# castaway_rp2040.net
KiCad netlist of a schematic drawn in EAGLE
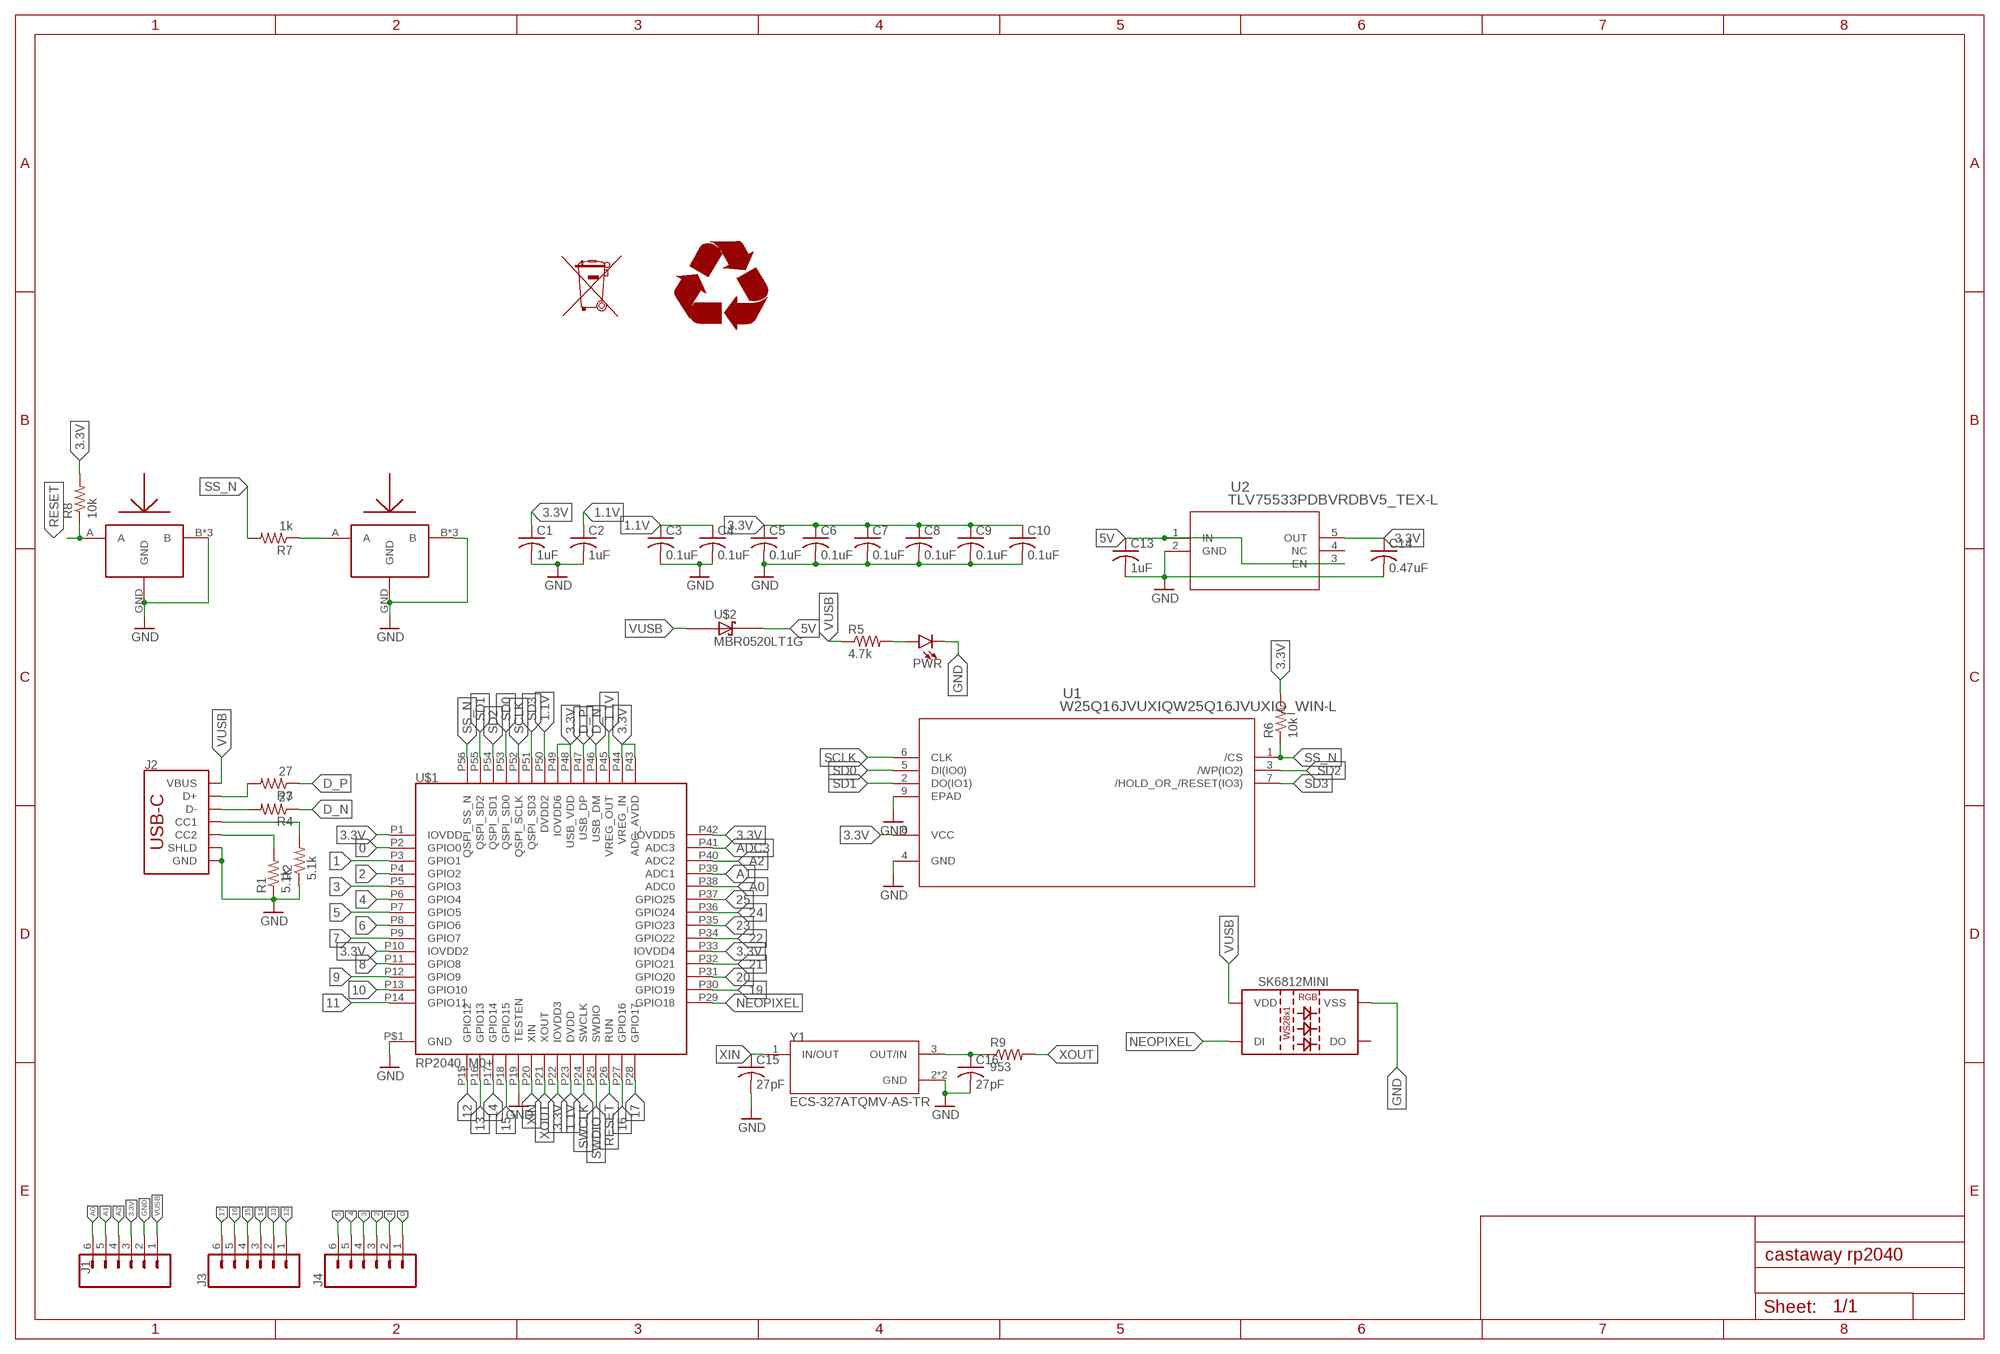
[diagram p0: schematic, sheet 1]

(export (version "E")
  (design (tool "Eeschema 10.0.6"))
  (components
    (comp (ref "C1")
      (value "1uF")
      (footprint "eagle-import:C0603")
      (libsource (lib "eagle-import") (part "C-USC0603"))
    )
    (comp (ref "C2")
      (value "1uF")
      (footprint "eagle-import:C0603")
      (libsource (lib "eagle-import") (part "C-USC0603"))
    )
    (comp (ref "C3")
      (value "0.1uF")
      (footprint "eagle-import:C0603")
      (libsource (lib "eagle-import") (part "C-USC0603"))
    )
    (comp (ref "C4")
      (value "0.1uF")
      (footprint "eagle-import:C0603")
      (libsource (lib "eagle-import") (part "C-USC0603"))
    )
    (comp (ref "C5")
      (value "0.1uF")
      (footprint "eagle-import:C0603")
      (libsource (lib "eagle-import") (part "C-USC0603"))
    )
    (comp (ref "C6")
      (value "0.1uF")
      (footprint "eagle-import:C0603")
      (libsource (lib "eagle-import") (part "C-USC0603"))
    )
    (comp (ref "C7")
      (value "0.1uF")
      (footprint "eagle-import:C0603")
      (libsource (lib "eagle-import") (part "C-USC0603"))
    )
    (comp (ref "C8")
      (value "0.1uF")
      (footprint "eagle-import:C0603")
      (libsource (lib "eagle-import") (part "C-USC0603"))
    )
    (comp (ref "C9")
      (value "0.1uF")
      (footprint "eagle-import:C0603")
      (libsource (lib "eagle-import") (part "C-USC0603"))
    )
    (comp (ref "C10")
      (value "0.1uF")
      (footprint "eagle-import:C0603")
      (libsource (lib "eagle-import") (part "C-USC0603"))
    )
    (comp (ref "C13")
      (value "1uF")
      (footprint "eagle-import:C0603")
      (libsource (lib "eagle-import") (part "C-USC0603"))
    )
    (comp (ref "C14")
      (value "0.47uF")
      (footprint "eagle-import:C0603")
      (libsource (lib "eagle-import") (part "C-USC0603"))
    )
    (comp (ref "C15")
      (value "27pF")
      (footprint "eagle-import:C0402")
      (libsource (lib "eagle-import") (part "C-USC0402"))
    )
    (comp (ref "C16")
      (value "27pF")
      (footprint "eagle-import:C0402")
      (libsource (lib "eagle-import") (part "C-USC0402"))
    )
    (comp (ref "J1")
      (value "CONN_06LONGPADS")
      (footprint "eagle-import:1X06_LONGPADS")
      (libsource (lib "eagle-import") (part "CONN_06LONGPADS"))
    )
    (comp (ref "J2")
      (value "USB_C_2-LAYER_PADS")
      (footprint "eagle-import:USB-C-16P-2LAYER-PADS")
      (libsource (lib "eagle-import") (part "USB_C_2-LAYER_PADS"))
    )
    (comp (ref "J3")
      (value "CONN_06LONGPADS")
      (footprint "eagle-import:1X06_LONGPADS")
      (libsource (lib "eagle-import") (part "CONN_06LONGPADS"))
    )
    (comp (ref "J4")
      (value "CONN_06LONGPADS")
      (footprint "eagle-import:1X06_LONGPADS")
      (libsource (lib "eagle-import") (part "CONN_06LONGPADS"))
    )
    (comp (ref "PWR")
      (value "LED0603")
      (footprint "eagle-import:LED-0603")
      (fields (field (name "SPICEPREFIX") "B"))
      (libsource (lib "eagle-import") (part "LED0603"))
    )
    (comp (ref "R1")
      (value "5.1k")
      (footprint "eagle-import:R0603")
      (libsource (lib "eagle-import") (part "R-US_R0603"))
    )
    (comp (ref "R2")
      (value "5.1k")
      (footprint "eagle-import:R0603")
      (libsource (lib "eagle-import") (part "R-US_R0603"))
    )
    (comp (ref "R3")
      (value "27")
      (footprint "eagle-import:R0603")
      (libsource (lib "eagle-import") (part "R-US_R0603"))
    )
    (comp (ref "R4")
      (value "27")
      (footprint "eagle-import:R0603")
      (libsource (lib "eagle-import") (part "R-US_R0603"))
    )
    (comp (ref "R5")
      (value "4.7k")
      (footprint "eagle-import:R0603")
      (libsource (lib "eagle-import") (part "R-US_R0603"))
    )
    (comp (ref "R6")
      (value "10k")
      (footprint "eagle-import:R0603")
      (libsource (lib "eagle-import") (part "R-US_R0603"))
    )
    (comp (ref "R7")
      (value "1k")
      (footprint "eagle-import:R0603")
      (libsource (lib "eagle-import") (part "R-US_R0603"))
    )
    (comp (ref "R8")
      (value "10k")
      (footprint "eagle-import:R0603")
      (libsource (lib "eagle-import") (part "R-US_R0603"))
    )
    (comp (ref "R9")
      (value "953")
      (footprint "eagle-import:R0402")
      (libsource (lib "eagle-import") (part "R-US_R0402"))
    )
    (comp (ref "SK6812MINI")
      (value "WS2812BWS2812B-3535")
      (footprint "eagle-import:WS2812-3535")
      (libsource (lib "eagle-import") (part "WS2812BWS2812B-3535"))
    )
    (comp (ref "U$1")
      (value "RP2040_M0+")
      (footprint "eagle-import:QFN-56")
      (libsource (lib "eagle-import") (part "RP2040_M0+"))
    )
    (comp (ref "U$2")
      (value "MBR0520LT1G")
      (footprint "eagle-import:SOD3716X117(SOD-123)")
      (fields (field (name "MF") "ON Semiconductor"))
      (libsource (lib "eagle-import") (part "MBR0520LT1G"))
    )
    (comp (ref "U$3")
      (value "SOF-232HST")
      (footprint "eagle-import:3.3X2.9")
      (libsource (lib "eagle-import") (part "SOF-232HST"))
    )
    (comp (ref "U$4")
      (value "SOF-232HST")
      (footprint "eagle-import:3.3X2.9")
      (libsource (lib "eagle-import") (part "SOF-232HST"))
    )
    (comp (ref "U1")
      (value "W25Q16JVUXIQW25Q16JVUXIQ_WIN-L")
      (footprint "eagle-import:W25Q16JVUXIQ_WIN-L")
      (fields
        (field (name "MANUFACTURER_PART_NUMBER") "W25Q16JVUXIQ")
        (field (name "COPYRIGHT") "Copyright (C) 2018 Accelerated Designs. All rights reserved")
      )
      (libsource (lib "eagle-import") (part "W25Q16JVUXIQW25Q16JVUXIQ_WIN-L"))
    )
    (comp (ref "U2")
      (value "TLV75533PDBVRDBV5_TEX-L")
      (footprint "eagle-import:DBV5_TEX-L")
      (fields
        (field (name "MANUFACTURER_PART_NUMBER") "TLV75533PDBVR")
        (field (name "COPYRIGHT") "Copyright (C) 2018 Accelerated Designs. All rights reserved")
      )
      (libsource (lib "eagle-import") (part "TLV75533PDBVRDBV5_TEX-L"))
    )
    (comp (ref "Y1")
      (value "ECS-327ATQMV-AS-TR")
      (footprint "eagle-import:XTAL_ECS-327ATQMV-AS-TR")
      (fields (field (name "DIGI-KEY_PART_NUMBER") "XC2826CT-ND") (field (name "MF") "ECS Inc."))
      (libsource (lib "eagle-import") (part "ECS-327ATQMV-AS-TR"))
    )
  )
  (nets
    (net (code "1") (name "0") (class "Default")
      (node (ref "J4") (pin "1") (pinfunction "1_1") (pintype "passive"))
      (node (ref "U$1") (pin "P2") (pinfunction "GPIO0_P2") (pintype "bidirectional"))
    )
    (net (code "2") (name "1") (class "Default")
      (node (ref "J4") (pin "2") (pinfunction "2_2") (pintype "passive"))
      (node (ref "U$1") (pin "P3") (pinfunction "GPIO1_P3") (pintype "bidirectional"))
    )
    (net (code "3") (name "1.1V") (class "Default")
      (node (ref "C2") (pin "1") (pinfunction "1_1") (pintype "passive"))
      (node (ref "C3") (pin "1") (pinfunction "1_1") (pintype "passive"))
      (node (ref "C4") (pin "1") (pinfunction "1_1") (pintype "passive"))
      (node (ref "U$1") (pin "P23") (pinfunction "DVDD_P23") (pintype "bidirectional"))
      (node (ref "U$1") (pin "P45") (pinfunction "VREG_OUT_P45") (pintype "bidirectional"))
      (node (ref "U$1") (pin "P50") (pinfunction "DVDD2_P50") (pintype "bidirectional"))
    )
    (net (code "4") (name "2") (class "Default")
      (node (ref "J4") (pin "3") (pinfunction "3_3") (pintype "passive"))
      (node (ref "U$1") (pin "P4") (pinfunction "GPIO2_P4") (pintype "bidirectional"))
    )
    (net (code "5") (name "3") (class "Default")
      (node (ref "J4") (pin "4") (pinfunction "4_4") (pintype "passive"))
      (node (ref "U$1") (pin "P5") (pinfunction "GPIO3_P5") (pintype "bidirectional"))
    )
    (net (code "6") (name "3.3V") (class "Default")
      (node (ref "C1") (pin "1") (pinfunction "1_1") (pintype "passive"))
      (node (ref "C10") (pin "1") (pinfunction "1_1") (pintype "passive"))
      (node (ref "C14") (pin "1") (pinfunction "1_1") (pintype "passive"))
      (node (ref "C5") (pin "1") (pinfunction "1_1") (pintype "passive"))
      (node (ref "C6") (pin "1") (pinfunction "1_1") (pintype "passive"))
      (node (ref "C7") (pin "1") (pinfunction "1_1") (pintype "passive"))
      (node (ref "C8") (pin "1") (pinfunction "1_1") (pintype "passive"))
      (node (ref "C9") (pin "1") (pinfunction "1_1") (pintype "passive"))
      (node (ref "J1") (pin "3") (pinfunction "3_3") (pintype "passive"))
      (node (ref "R6") (pin "2") (pinfunction "2_2") (pintype "passive"))
      (node (ref "R8") (pin "2") (pinfunction "2_2") (pintype "passive"))
      (node (ref "U$1") (pin "P1") (pinfunction "IOVDD_P1") (pintype "bidirectional"))
      (node (ref "U$1") (pin "P10") (pinfunction "IOVDD2_P10") (pintype "bidirectional"))
      (node (ref "U$1") (pin "P22") (pinfunction "IOVDD3_P22") (pintype "bidirectional"))
      (node (ref "U$1") (pin "P33") (pinfunction "IOVDD4_P33") (pintype "bidirectional"))
      (node (ref "U$1") (pin "P42") (pinfunction "IOVDD5_P42") (pintype "bidirectional"))
      (node (ref "U$1") (pin "P43") (pinfunction "ADC_AVDD_P43") (pintype "bidirectional"))
      (node (ref "U$1") (pin "P44") (pinfunction "VREG_IN_P44") (pintype "bidirectional"))
      (node (ref "U$1") (pin "P48") (pinfunction "USB_VDD_P48") (pintype "bidirectional"))
      (node (ref "U$1") (pin "P49") (pinfunction "IOVDD6_P49") (pintype "bidirectional"))
      (node (ref "U1") (pin "8") (pinfunction "VCC_8") (pintype "passive"))
      (node (ref "U2") (pin "5") (pinfunction "OUT_5") (pintype "output"))
    )
    (net (code "7") (name "4") (class "Default")
      (node (ref "J4") (pin "5") (pinfunction "5_5") (pintype "passive"))
      (node (ref "U$1") (pin "P6") (pinfunction "GPIO4_P6") (pintype "bidirectional"))
    )
    (net (code "8") (name "5") (class "Default")
      (node (ref "J4") (pin "6") (pinfunction "6_6") (pintype "passive"))
      (node (ref "U$1") (pin "P7") (pinfunction "GPIO5_P7") (pintype "bidirectional"))
    )
    (net (code "9") (name "5V") (class "Default")
      (node (ref "C13") (pin "1") (pinfunction "1_1") (pintype "passive"))
      (node (ref "U$2") (pin "1") (pinfunction "C_1") (pintype "passive"))
      (node (ref "U2") (pin "1") (pinfunction "IN_1") (pintype "input"))
      (node (ref "U2") (pin "3") (pinfunction "EN_3") (pintype "input"))
    )
    (net (code "10") (name "6") (class "Default")
      (node (ref "U$1") (pin "P8") (pinfunction "GPIO6_P8") (pintype "bidirectional"))
    )
    (net (code "11") (name "7") (class "Default")
      (node (ref "U$1") (pin "P9") (pinfunction "GPIO7_P9") (pintype "bidirectional"))
    )
    (net (code "12") (name "8") (class "Default")
      (node (ref "U$1") (pin "P11") (pinfunction "GPIO8_P11") (pintype "bidirectional"))
    )
    (net (code "13") (name "9") (class "Default")
      (node (ref "U$1") (pin "P12") (pinfunction "GPIO9_P12") (pintype "bidirectional"))
    )
    (net (code "14") (name "10") (class "Default")
      (node (ref "U$1") (pin "P13") (pinfunction "GPIO10_P13") (pintype "bidirectional"))
    )
    (net (code "15") (name "11") (class "Default")
      (node (ref "U$1") (pin "P14") (pinfunction "GPIO11_P14") (pintype "bidirectional"))
    )
    (net (code "16") (name "12") (class "Default")
      (node (ref "J3") (pin "1") (pinfunction "1_1") (pintype "passive"))
      (node (ref "U$1") (pin "P15") (pinfunction "GPIO12_P15") (pintype "bidirectional"))
    )
    (net (code "17") (name "13") (class "Default")
      (node (ref "J3") (pin "2") (pinfunction "2_2") (pintype "passive"))
      (node (ref "U$1") (pin "P16") (pinfunction "GPIO13_P16") (pintype "bidirectional"))
    )
    (net (code "18") (name "14") (class "Default")
      (node (ref "J3") (pin "3") (pinfunction "3_3") (pintype "passive"))
      (node (ref "U$1") (pin "P17") (pinfunction "GPIO14_P17") (pintype "bidirectional"))
    )
    (net (code "19") (name "15") (class "Default")
      (node (ref "J3") (pin "4") (pinfunction "4_4") (pintype "passive"))
      (node (ref "U$1") (pin "P18") (pinfunction "GPIO15_P18") (pintype "bidirectional"))
    )
    (net (code "20") (name "16") (class "Default")
      (node (ref "J3") (pin "5") (pinfunction "5_5") (pintype "passive"))
      (node (ref "U$1") (pin "P27") (pinfunction "GPIO16_P27") (pintype "bidirectional"))
    )
    (net (code "21") (name "17") (class "Default")
      (node (ref "J3") (pin "6") (pinfunction "6_6") (pintype "passive"))
      (node (ref "U$1") (pin "P28") (pinfunction "GPIO17_P28") (pintype "bidirectional"))
    )
    (net (code "22") (name "19") (class "Default")
      (node (ref "U$1") (pin "P30") (pinfunction "GPIO19_P30") (pintype "bidirectional"))
    )
    (net (code "23") (name "20") (class "Default")
      (node (ref "U$1") (pin "P31") (pinfunction "GPIO20_P31") (pintype "bidirectional"))
    )
    (net (code "24") (name "21") (class "Default")
      (node (ref "U$1") (pin "P32") (pinfunction "GPIO21_P32") (pintype "bidirectional"))
    )
    (net (code "25") (name "22") (class "Default")
      (node (ref "U$1") (pin "P34") (pinfunction "GPIO22_P34") (pintype "bidirectional"))
    )
    (net (code "26") (name "23") (class "Default")
      (node (ref "U$1") (pin "P35") (pinfunction "GPIO23_P35") (pintype "bidirectional"))
    )
    (net (code "27") (name "24") (class "Default")
      (node (ref "U$1") (pin "P36") (pinfunction "GPIO24_P36") (pintype "bidirectional"))
    )
    (net (code "28") (name "25") (class "Default")
      (node (ref "U$1") (pin "P37") (pinfunction "GPIO25_P37") (pintype "bidirectional"))
    )
    (net (code "29") (name "A0") (class "Default")
      (node (ref "J1") (pin "6") (pinfunction "6_6") (pintype "passive"))
      (node (ref "U$1") (pin "P38") (pinfunction "ADC0_P38") (pintype "bidirectional"))
    )
    (net (code "30") (name "A1") (class "Default")
      (node (ref "J1") (pin "5") (pinfunction "5_5") (pintype "passive"))
      (node (ref "U$1") (pin "P39") (pinfunction "ADC1_P39") (pintype "bidirectional"))
    )
    (net (code "31") (name "A2") (class "Default")
      (node (ref "J1") (pin "4") (pinfunction "4_4") (pintype "passive"))
      (node (ref "U$1") (pin "P40") (pinfunction "ADC2_P40") (pintype "bidirectional"))
    )
    (net (code "32") (name "ADC3") (class "Default")
      (node (ref "U$1") (pin "P41") (pinfunction "ADC3_P41") (pintype "bidirectional"))
    )
    (net (code "33") (name "D_N") (class "Default")
      (node (ref "R4") (pin "1") (pinfunction "1_1") (pintype "passive"))
      (node (ref "U$1") (pin "P46") (pinfunction "USB_DM_P46") (pintype "bidirectional"))
    )
    (net (code "34") (name "D_P") (class "Default")
      (node (ref "R3") (pin "1") (pinfunction "1_1") (pintype "passive"))
      (node (ref "U$1") (pin "P47") (pinfunction "USB_DP_P47") (pintype "bidirectional"))
    )
    (net (code "35") (name "GND") (class "Default")
      (node (ref "C1") (pin "2") (pinfunction "2_2") (pintype "passive"))
      (node (ref "C10") (pin "2") (pinfunction "2_2") (pintype "passive"))
      (node (ref "C13") (pin "2") (pinfunction "2_2") (pintype "passive"))
      (node (ref "C14") (pin "2") (pinfunction "2_2") (pintype "passive"))
      (node (ref "C15") (pin "2") (pinfunction "2_2") (pintype "passive"))
      (node (ref "C16") (pin "2") (pinfunction "2_2") (pintype "passive"))
      (node (ref "C2") (pin "2") (pinfunction "2_2") (pintype "passive"))
      (node (ref "C3") (pin "2") (pinfunction "2_2") (pintype "passive"))
      (node (ref "C4") (pin "2") (pinfunction "2_2") (pintype "passive"))
      (node (ref "C5") (pin "2") (pinfunction "2_2") (pintype "passive"))
      (node (ref "C6") (pin "2") (pinfunction "2_2") (pintype "passive"))
      (node (ref "C7") (pin "2") (pinfunction "2_2") (pintype "passive"))
      (node (ref "C8") (pin "2") (pinfunction "2_2") (pintype "passive"))
      (node (ref "C9") (pin "2") (pinfunction "2_2") (pintype "passive"))
      (node (ref "J1") (pin "2") (pinfunction "2_2") (pintype "passive"))
      (node (ref "J2") (pin "GND") (pinfunction "GND_GND") (pintype "bidirectional"))
      (node (ref "J2") (pin "GND2") (pinfunction "GND_GND2") (pintype "bidirectional"))
      (node (ref "J2") (pin "P$1") (pinfunction "SHLD_P$1") (pintype "bidirectional"))
      (node (ref "J2") (pin "P$2") (pinfunction "SHLD_P$2") (pintype "bidirectional"))
      (node (ref "J2") (pin "P$3") (pinfunction "SHLD_P$3") (pintype "bidirectional"))
      (node (ref "J2") (pin "P$4") (pinfunction "SHLD_P$4") (pintype "bidirectional"))
      (node (ref "J2") (pin "SHLD1") (pinfunction "SHLD_SHLD1") (pintype "bidirectional"))
      (node (ref "J2") (pin "SHLD2") (pinfunction "SHLD_SHLD2") (pintype "bidirectional"))
      (node (ref "J2") (pin "SHLD3") (pinfunction "SHLD_SHLD3") (pintype "bidirectional"))
      (node (ref "J2") (pin "SHLD4") (pinfunction "SHLD_SHLD4") (pintype "bidirectional"))
      (node (ref "PWR") (pin "C") (pinfunction "C_C") (pintype "passive"))
      (node (ref "R1") (pin "1") (pinfunction "1_1") (pintype "passive"))
      (node (ref "R2") (pin "1") (pinfunction "1_1") (pintype "passive"))
      (node (ref "SK6812MINI") (pin "VSS") (pinfunction "VSS_VSS") (pintype "bidirectional"))
      (node (ref "U$1") (pin "P$1") (pinfunction "GND_P$1") (pintype "bidirectional"))
      (node (ref "U$1") (pin "P19") (pinfunction "TESTEN_P19") (pintype "bidirectional"))
      (node (ref "U$3") (pin "B") (pinfunction "B_B") (pintype "bidirectional"))
      (node (ref "U$3") (pin "B2") (pinfunction "B_B2") (pintype "bidirectional"))
      (node (ref "U$3") (pin "B3") (pinfunction "B_B3") (pintype "bidirectional"))
      (node (ref "U$3") (pin "GND") (pinfunction "GND_GND") (pintype "bidirectional"))
      (node (ref "U$4") (pin "B") (pinfunction "B_B") (pintype "bidirectional"))
      (node (ref "U$4") (pin "B2") (pinfunction "B_B2") (pintype "bidirectional"))
      (node (ref "U$4") (pin "B3") (pinfunction "B_B3") (pintype "bidirectional"))
      (node (ref "U$4") (pin "GND") (pinfunction "GND_GND") (pintype "bidirectional"))
      (node (ref "U1") (pin "4") (pinfunction "GND_4") (pintype "passive"))
      (node (ref "U1") (pin "9") (pinfunction "EPAD_9") (pintype "passive"))
      (node (ref "U2") (pin "2") (pinfunction "GND_2") (pintype "power_in"))
      (node (ref "Y1") (pin "2") (pinfunction "GND_2") (pintype "power_in"))
      (node (ref "Y1") (pin "4") (pinfunction "GND_4") (pintype "power_in"))
    )
    (net (code "36") (name "NEOPIXEL") (class "Default")
      (node (ref "SK6812MINI") (pin "DIN") (pinfunction "DI_DIN") (pintype "bidirectional"))
      (node (ref "U$1") (pin "P29") (pinfunction "GPIO18_P29") (pintype "bidirectional"))
    )
    (net (code "37") (name "Net-(J2-CC1)") (class "Default")
      (node (ref "J2") (pin "A5") (pinfunction "CC1_A5") (pintype "bidirectional"))
      (node (ref "R2") (pin "2") (pinfunction "2_2") (pintype "passive"))
    )
    (net (code "38") (name "Net-(J2-CC2)") (class "Default")
      (node (ref "J2") (pin "B5") (pinfunction "CC2_B5") (pintype "bidirectional"))
      (node (ref "R1") (pin "2") (pinfunction "2_2") (pintype "passive"))
    )
    (net (code "39") (name "Net-(J2-D+-PadA6)") (class "Default")
      (node (ref "J2") (pin "A6") (pinfunction "D+_A6") (pintype "bidirectional"))
      (node (ref "J2") (pin "B6") (pinfunction "D+_B6") (pintype "bidirectional"))
      (node (ref "R3") (pin "2") (pinfunction "2_2") (pintype "passive"))
    )
    (net (code "40") (name "Net-(J2-D--PadA7)") (class "Default")
      (node (ref "J2") (pin "A7") (pinfunction "D-_A7") (pintype "bidirectional"))
      (node (ref "J2") (pin "B7") (pinfunction "D-_B7") (pintype "bidirectional"))
      (node (ref "R4") (pin "2") (pinfunction "2_2") (pintype "passive"))
    )
    (net (code "41") (name "Net-(PWR-PadA)") (class "Default")
      (node (ref "PWR") (pin "A") (pinfunction "A_A") (pintype "passive"))
      (node (ref "R5") (pin "2") (pinfunction "2_2") (pintype "passive"))
    )
    (net (code "42") (name "Net-(R7-Pad1)") (class "Default")
      (node (ref "R7") (pin "1") (pinfunction "1_1") (pintype "passive"))
      (node (ref "U$4") (pin "A") (pinfunction "A_A") (pintype "bidirectional"))
    )
    (net (code "43") (name "Net-(Y1-OUT{slash}IN)") (class "Default")
      (node (ref "C16") (pin "1") (pinfunction "1_1") (pintype "passive"))
      (node (ref "R9") (pin "1") (pinfunction "1_1") (pintype "passive"))
      (node (ref "Y1") (pin "3") (pinfunction "OUT/IN_3") (pintype "bidirectional"))
    )
    (net (code "44") (name "RESET") (class "Default")
      (node (ref "R8") (pin "1") (pinfunction "1_1") (pintype "passive"))
      (node (ref "U$1") (pin "P26") (pinfunction "RUN_P26") (pintype "bidirectional"))
      (node (ref "U$3") (pin "A") (pinfunction "A_A") (pintype "bidirectional"))
    )
    (net (code "45") (name "SCLK") (class "Default")
      (node (ref "U$1") (pin "P52") (pinfunction "QSPI_SCLK_P52") (pintype "bidirectional"))
      (node (ref "U1") (pin "6") (pinfunction "CLK_6") (pintype "passive"))
    )
    (net (code "46") (name "SD0") (class "Default")
      (node (ref "U$1") (pin "P53") (pinfunction "QSPI_SD0_P53") (pintype "bidirectional"))
      (node (ref "U1") (pin "5") (pinfunction "DI(IO0)_5") (pintype "passive"))
    )
    (net (code "47") (name "SD1") (class "Default")
      (node (ref "U$1") (pin "P55") (pinfunction "QSPI_SD2_P55") (pintype "bidirectional"))
      (node (ref "U1") (pin "2") (pinfunction "DO(IO1)_2") (pintype "passive"))
    )
    (net (code "48") (name "SD2") (class "Default")
      (node (ref "U$1") (pin "P54") (pinfunction "QSPI_SD1_P54") (pintype "bidirectional"))
      (node (ref "U1") (pin "3") (pinfunction "/WP(IO2)_3") (pintype "passive"))
    )
    (net (code "49") (name "SD3") (class "Default")
      (node (ref "U$1") (pin "P51") (pinfunction "QSPI_SD3_P51") (pintype "bidirectional"))
      (node (ref "U1") (pin "7") (pinfunction "/HOLD_OR_/RESET(IO3)_7") (pintype "passive"))
    )
    (net (code "50") (name "SS_N") (class "Default")
      (node (ref "R6") (pin "1") (pinfunction "1_1") (pintype "passive"))
      (node (ref "R7") (pin "2") (pinfunction "2_2") (pintype "passive"))
      (node (ref "U$1") (pin "P56") (pinfunction "QSPI_SS_N_P56") (pintype "bidirectional"))
      (node (ref "U1") (pin "1") (pinfunction "/CS_1") (pintype "passive"))
    )
    (net (code "51") (name "SWCLK") (class "Default")
      (node (ref "U$1") (pin "P24") (pinfunction "SWCLK_P24") (pintype "bidirectional"))
    )
    (net (code "52") (name "SWDIO") (class "Default")
      (node (ref "U$1") (pin "P25") (pinfunction "SWDIO_P25") (pintype "bidirectional"))
    )
    (net (code "53") (name "VUSB") (class "Default")
      (node (ref "J1") (pin "1") (pinfunction "1_1") (pintype "passive"))
      (node (ref "J2") (pin "VBUS1") (pinfunction "VBUS_VBUS1") (pintype "bidirectional"))
      (node (ref "J2") (pin "VBUS2") (pinfunction "VBUS_VBUS2") (pintype "bidirectional"))
      (node (ref "R5") (pin "1") (pinfunction "1_1") (pintype "passive"))
      (node (ref "SK6812MINI") (pin "VDD") (pinfunction "VDD_VDD") (pintype "bidirectional"))
      (node (ref "U$2") (pin "2") (pinfunction "A_2") (pintype "passive"))
    )
    (net (code "54") (name "XIN") (class "Default")
      (node (ref "C15") (pin "1") (pinfunction "1_1") (pintype "passive"))
      (node (ref "U$1") (pin "P20") (pinfunction "XIN_P20") (pintype "bidirectional"))
      (node (ref "Y1") (pin "1") (pinfunction "IN/OUT_1") (pintype "bidirectional"))
    )
    (net (code "55") (name "XOUT") (class "Default")
      (node (ref "R9") (pin "2") (pinfunction "2_2") (pintype "passive"))
      (node (ref "U$1") (pin "P21") (pinfunction "XOUT_P21") (pintype "bidirectional"))
    )
    (net (code "56") (name "unconnected-(SK6812MINI-DO-PadDOUT)") (class "Default")
      (node (ref "SK6812MINI") (pin "DOUT") (pinfunction "DO_DOUT") (pintype "bidirectional"))
    )
    (net (code "57") (name "unconnected-(U2-NC-Pad4)") (class "Default")
      (node (ref "U2") (pin "4") (pinfunction "NC_4") (pintype "no_connect"))
    )
  )
)
